# Main.net
KiCad netlist of a schematic drawn in Altium Designer
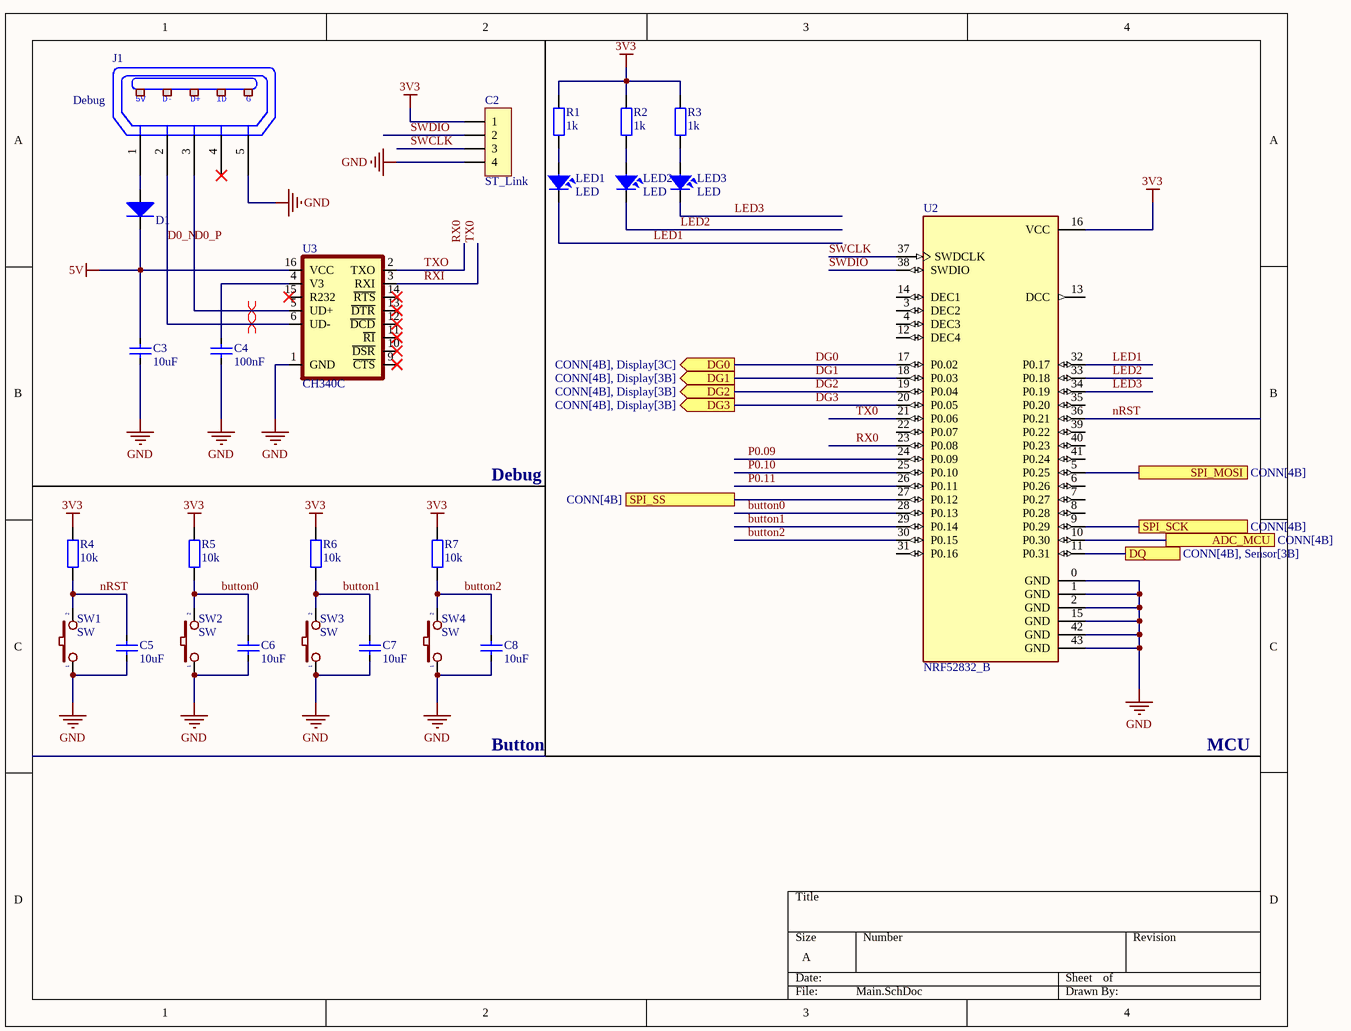
[diagram p0: Main.SchDoc]

(export (version "E")
  (design (tool "Eeschema 10.0.6"))
  (components
    (comp (ref "C2")
      (value "ST_Link")
      (footprint "J4-D1T")
      (description "WR-PHD 2.00 mm Socket Header")
      (fields
        (field (name "MANUFACTURER") "Würth Elektronik eiSos GmbH")
        (field (name "PARTNO") "62000411821")
        (field (name "CREATED BY") "Karrer Zheng")
      )
      (libsource (lib "Main") (part "JP4x1-2.0"))
    )
    (comp (ref "C3")
      (value "10uF")
      (footprint "CAP_0805")
      (description "Capacitor")
      (fields (field (name "PUBLISHER") "Altium Limited"))
      (libsource (lib "My Library") (part "CapSMD"))
    )
    (comp (ref "C4")
      (value "100nF")
      (footprint "CAP_0805")
      (description "Capacitor")
      (fields (field (name "PUBLISHER") "Altium Limited"))
      (libsource (lib "My Library") (part "CapSMD"))
    )
    (comp (ref "C5")
      (value "10uF")
      (footprint "CAP_0805")
      (description "Capacitor")
      (fields (field (name "PUBLISHER") "Altium Limited"))
      (libsource (lib "My Library") (part "CapSMD"))
    )
    (comp (ref "C6")
      (value "10uF")
      (footprint "CAP_0805")
      (description "Capacitor")
      (fields (field (name "PUBLISHER") "Altium Limited"))
      (libsource (lib "My Library") (part "CapSMD"))
    )
    (comp (ref "C7")
      (value "10uF")
      (footprint "CAP_0805")
      (description "Capacitor")
      (fields (field (name "PUBLISHER") "Altium Limited"))
      (libsource (lib "My Library") (part "CapSMD"))
    )
    (comp (ref "C8")
      (value "10uF")
      (footprint "CAP_0805")
      (description "Capacitor")
      (fields (field (name "PUBLISHER") "Altium Limited"))
      (libsource (lib "My Library") (part "CapSMD"))
    )
    (comp (ref "D1")
      (value "Diode SMD")
      (footprint "DIO-214AC(SMA)")
      (description "Default Diode")
      (fields (field (name "PUBLISHER") "Altium Limited"))
      (libsource (lib "My Library") (part "Diode SMD"))
    )
    (comp (ref "J1")
      (value "Debug")
      (footprint "USB-M1")
      (fields
        (field (name "MANUFACTURER") "FCI")
        (field (name "MANUFACTURER PART NUMBER") "10118193-0001LF")
        (field (name ".CREATOR") "MM")
        (field (name ".CHECKED PCB") "RF")
        (field (name ".CHECKED SCH") "MM")
      )
      (libsource (lib "My Library") (part "USB-5"))
    )
    (comp (ref "LED1")
      (value "LED")
      (footprint "LED-0805-Red")
      (description "LED Single colour Green and Red")
      (libsource (lib "My Library") (part "LED"))
    )
    (comp (ref "LED2")
      (value "LED")
      (footprint "LED-0805-Yellow")
      (description "LED Single colour Green and Red")
      (libsource (lib "My Library") (part "LED"))
    )
    (comp (ref "LED3")
      (value "LED")
      (footprint "LED-0805-Green")
      (description "LED Single colour Green and Red")
      (libsource (lib "My Library") (part "LED"))
    )
    (comp (ref "R1")
      (value "1k")
      (footprint "RES-SMD-0805")
      (description "Resistor SMD")
      (fields
        (field (name "MANUFACTURER") "Generic Components")
        (field (name "PUBLISHER") "Altium Hobart Technology Centre")
      )
      (libsource (lib "My Library") (part "Resistor - SMD"))
    )
    (comp (ref "R2")
      (value "1k")
      (footprint "RES-SMD-0805")
      (description "Resistor SMD")
      (fields
        (field (name "MANUFACTURER") "Generic Components")
        (field (name "PUBLISHER") "Altium Hobart Technology Centre")
      )
      (libsource (lib "My Library") (part "Resistor - SMD"))
    )
    (comp (ref "R3")
      (value "1k")
      (footprint "RES-SMD-0805")
      (description "Resistor SMD")
      (fields
        (field (name "MANUFACTURER") "Generic Components")
        (field (name "PUBLISHER") "Altium Hobart Technology Centre")
      )
      (libsource (lib "My Library") (part "Resistor - SMD"))
    )
    (comp (ref "R4")
      (value "10k")
      (footprint "RES-SMD-0805")
      (description "Resistor SMD")
      (fields
        (field (name "MANUFACTURER") "Generic Components")
        (field (name "PUBLISHER") "Altium Hobart Technology Centre")
      )
      (libsource (lib "My Library") (part "Resistor - SMD"))
    )
    (comp (ref "R5")
      (value "10k")
      (footprint "RES-SMD-0805")
      (description "Resistor SMD")
      (fields
        (field (name "MANUFACTURER") "Generic Components")
        (field (name "PUBLISHER") "Altium Hobart Technology Centre")
      )
      (libsource (lib "My Library") (part "Resistor - SMD"))
    )
    (comp (ref "R6")
      (value "10k")
      (footprint "RES-SMD-0805")
      (description "Resistor SMD")
      (fields
        (field (name "MANUFACTURER") "Generic Components")
        (field (name "PUBLISHER") "Altium Hobart Technology Centre")
      )
      (libsource (lib "My Library") (part "Resistor - SMD"))
    )
    (comp (ref "R7")
      (value "10k")
      (footprint "RES-SMD-0805")
      (description "Resistor SMD")
      (fields
        (field (name "MANUFACTURER") "Generic Components")
        (field (name "PUBLISHER") "Altium Hobart Technology Centre")
      )
      (libsource (lib "My Library") (part "Resistor - SMD"))
    )
    (comp (ref "SW1")
      (value "SW")
      (footprint "SW 3x2x4")
      (description "Switch button 2 pin")
      (libsource (lib "My Library") (part "SW2"))
    )
    (comp (ref "SW2")
      (value "SW")
      (footprint "SW2")
      (description "Switch button 2 pin")
      (libsource (lib "My Library") (part "SW2"))
    )
    (comp (ref "SW3")
      (value "SW")
      (footprint "SW2")
      (description "Switch button 2 pin")
      (libsource (lib "My Library") (part "SW2"))
    )
    (comp (ref "SW4")
      (value "SW")
      (footprint "SW2")
      (description "Switch button 2 pin")
      (libsource (lib "My Library") (part "SW2"))
    )
    (comp (ref "U2")
      (value "NRF52832_B")
      (footprint "NRF52832_B")
      (description "https://www.ebyte.com/product-view-news.aspx?id=239&=ds-tm")
      (libsource (lib "Main") (part "NRF52832_B"))
    )
    (comp (ref "U3")
      (value "CH340C")
      (footprint "SOP-16")
      (description "USB to serial chip CH340")
      (fields (field (name "MF") "WCH"))
      (libsource (lib "My Library") (part "CH340C"))
    )
  )
  (nets
    (net (code "1") (name "/ADC_MCU") (class "Default")
      (node (ref "U2") (pin "10") (pinfunction "P0.30_10") (pintype "bidirectional"))
    )
    (net (code "2") (name "/D0_N") (class "Default")
      (node (ref "J1") (pin "2") (pinfunction "P2_2") (pintype "passive"))
      (node (ref "U3") (pin "6") (pinfunction "UD-_6") (pintype "bidirectional"))
    )
    (net (code "3") (name "/D0_P") (class "Default")
      (node (ref "J1") (pin "3") (pinfunction "P3_3") (pintype "passive"))
      (node (ref "U3") (pin "5") (pinfunction "UD+_5") (pintype "bidirectional"))
    )
    (net (code "4") (name "/DG0") (class "Default")
      (node (ref "U2") (pin "17") (pinfunction "P0.02_17") (pintype "bidirectional"))
    )
    (net (code "5") (name "/DG1") (class "Default")
      (node (ref "U2") (pin "18") (pinfunction "P0.03_18") (pintype "bidirectional"))
    )
    (net (code "6") (name "/DG2") (class "Default")
      (node (ref "U2") (pin "19") (pinfunction "P0.04_19") (pintype "bidirectional"))
    )
    (net (code "7") (name "/DG3") (class "Default")
      (node (ref "U2") (pin "20") (pinfunction "P0.05_20") (pintype "bidirectional"))
    )
    (net (code "8") (name "/DQ") (class "Default")
      (node (ref "U2") (pin "11") (pinfunction "P0.31_11") (pintype "bidirectional"))
    )
    (net (code "9") (name "/LED1") (class "Default")
      (node (ref "LED1") (pin "2") (pinfunction "2_2") (pintype "passive"))
      (node (ref "U2") (pin "32") (pinfunction "P0.17_32") (pintype "bidirectional"))
    )
    (net (code "10") (name "/LED2") (class "Default")
      (node (ref "LED2") (pin "2") (pinfunction "2_2") (pintype "passive"))
      (node (ref "U2") (pin "33") (pinfunction "P0.18_33") (pintype "bidirectional"))
    )
    (net (code "11") (name "/LED3") (class "Default")
      (node (ref "LED3") (pin "2") (pinfunction "2_2") (pintype "passive"))
      (node (ref "U2") (pin "34") (pinfunction "P0.19_34") (pintype "bidirectional"))
    )
    (net (code "12") (name "/P0.09") (class "Default")
      (node (ref "U2") (pin "24") (pinfunction "P0.09_24") (pintype "bidirectional"))
    )
    (net (code "13") (name "/P0.10") (class "Default")
      (node (ref "U2") (pin "25") (pinfunction "P0.10_25") (pintype "bidirectional"))
    )
    (net (code "14") (name "/P0.11") (class "Default")
      (node (ref "U2") (pin "26") (pinfunction "P0.11_26") (pintype "bidirectional"))
    )
    (net (code "15") (name "/RX0") (class "Default")
      (node (ref "U2") (pin "23") (pinfunction "P0.08_23") (pintype "bidirectional"))
      (node (ref "U3") (pin "2") (pinfunction "TXO_2") (pintype "bidirectional"))
    )
    (net (code "16") (name "/RXI") (class "Default")
      (node (ref "U2") (pin "21") (pinfunction "P0.06_21") (pintype "bidirectional"))
      (node (ref "U3") (pin "3") (pinfunction "RXI_3") (pintype "bidirectional"))
    )
    (net (code "17") (name "/SPI_MOSI") (class "Default")
      (node (ref "U2") (pin "5") (pinfunction "P0.25_5") (pintype "bidirectional"))
    )
    (net (code "18") (name "/SPI_SCK") (class "Default")
      (node (ref "U2") (pin "9") (pinfunction "P0.29_9") (pintype "bidirectional"))
    )
    (net (code "19") (name "/SPI_SS") (class "Default")
      (node (ref "U2") (pin "27") (pinfunction "P0.12_27") (pintype "bidirectional"))
    )
    (net (code "20") (name "/SWCLK") (class "Default")
      (node (ref "C2") (pin "3") (pinfunction "3_3") (pintype "passive"))
      (node (ref "U2") (pin "37") (pinfunction "SWDCLK_37") (pintype "input"))
    )
    (net (code "21") (name "/SWDIO") (class "Default")
      (node (ref "C2") (pin "2") (pinfunction "2_2") (pintype "passive"))
      (node (ref "U2") (pin "38") (pinfunction "SWDIO_38") (pintype "bidirectional"))
    )
    (net (code "22") (name "/button0") (class "Default")
      (node (ref "C6") (pin "2") (pinfunction "2_2") (pintype "passive"))
      (node (ref "R5") (pin "2") (pinfunction "2_2") (pintype "passive"))
      (node (ref "SW2") (pin "2") (pinfunction "2_2") (pintype "passive"))
      (node (ref "U2") (pin "28") (pinfunction "P0.13_28") (pintype "bidirectional"))
    )
    (net (code "23") (name "/button1") (class "Default")
      (node (ref "C7") (pin "2") (pinfunction "2_2") (pintype "passive"))
      (node (ref "R6") (pin "2") (pinfunction "2_2") (pintype "passive"))
      (node (ref "SW3") (pin "2") (pinfunction "2_2") (pintype "passive"))
      (node (ref "U2") (pin "29") (pinfunction "P0.14_29") (pintype "bidirectional"))
    )
    (net (code "24") (name "/button2") (class "Default")
      (node (ref "C8") (pin "2") (pinfunction "2_2") (pintype "passive"))
      (node (ref "R7") (pin "2") (pinfunction "2_2") (pintype "passive"))
      (node (ref "SW4") (pin "2") (pinfunction "2_2") (pintype "passive"))
      (node (ref "U2") (pin "30") (pinfunction "P0.15_30") (pintype "bidirectional"))
    )
    (net (code "25") (name "/nRST") (class "Default")
      (node (ref "C5") (pin "2") (pinfunction "2_2") (pintype "passive"))
      (node (ref "R4") (pin "2") (pinfunction "2_2") (pintype "passive"))
      (node (ref "SW1") (pin "2") (pinfunction "2_2") (pintype "passive"))
      (node (ref "U2") (pin "36") (pinfunction "P0.21_36") (pintype "bidirectional"))
    )
    (net (code "26") (name "3V3") (class "Default")
      (node (ref "C2") (pin "1") (pinfunction "1_1") (pintype "passive"))
      (node (ref "R1") (pin "1") (pinfunction "1_1") (pintype "passive"))
      (node (ref "R2") (pin "1") (pinfunction "1_1") (pintype "passive"))
      (node (ref "R3") (pin "1") (pinfunction "1_1") (pintype "passive"))
      (node (ref "R4") (pin "1") (pinfunction "1_1") (pintype "passive"))
      (node (ref "R5") (pin "1") (pinfunction "1_1") (pintype "passive"))
      (node (ref "R6") (pin "1") (pinfunction "1_1") (pintype "passive"))
      (node (ref "R7") (pin "1") (pinfunction "1_1") (pintype "passive"))
      (node (ref "U2") (pin "16") (pinfunction "VCC_16") (pintype "power_in"))
    )
    (net (code "27") (name "5V") (class "Default")
      (node (ref "C3") (pin "2") (pinfunction "2_2") (pintype "passive"))
      (node (ref "D1") (pin "2") (pinfunction "K_2") (pintype "passive"))
      (node (ref "U3") (pin "16") (pinfunction "VCC_16") (pintype "bidirectional"))
    )
    (net (code "28") (name "GND") (class "Default")
      (node (ref "C2") (pin "4") (pinfunction "4_4") (pintype "passive"))
      (node (ref "C3") (pin "1") (pinfunction "1_1") (pintype "passive"))
      (node (ref "C4") (pin "1") (pinfunction "1_1") (pintype "passive"))
      (node (ref "C5") (pin "1") (pinfunction "1_1") (pintype "passive"))
      (node (ref "C6") (pin "1") (pinfunction "1_1") (pintype "passive"))
      (node (ref "C7") (pin "1") (pinfunction "1_1") (pintype "passive"))
      (node (ref "C8") (pin "1") (pinfunction "1_1") (pintype "passive"))
      (node (ref "J1") (pin "5") (pinfunction "P5_5") (pintype "passive"))
      (node (ref "SW1") (pin "1") (pinfunction "1_1") (pintype "passive"))
      (node (ref "SW2") (pin "1") (pinfunction "1_1") (pintype "passive"))
      (node (ref "SW3") (pin "1") (pinfunction "1_1") (pintype "passive"))
      (node (ref "SW4") (pin "1") (pinfunction "1_1") (pintype "passive"))
      (node (ref "U2") (pin "0") (pinfunction "GND_0") (pintype "power_in"))
      (node (ref "U2") (pin "1") (pinfunction "GND_1") (pintype "power_in"))
      (node (ref "U2") (pin "15") (pinfunction "GND_15") (pintype "power_in"))
      (node (ref "U2") (pin "2") (pinfunction "GND_2") (pintype "power_in"))
      (node (ref "U2") (pin "42") (pinfunction "GND_42") (pintype "power_in"))
      (node (ref "U2") (pin "43") (pinfunction "GND_43") (pintype "power_in"))
      (node (ref "U3") (pin "1") (pinfunction "GND_1") (pintype "bidirectional"))
    )
    (net (code "29") (name "Net-(D1-A)") (class "Default")
      (node (ref "D1") (pin "1") (pinfunction "A_1") (pintype "passive"))
      (node (ref "J1") (pin "1") (pinfunction "P1_1") (pintype "passive"))
    )
    (net (code "30") (name "Net-(LED1-Pad1)") (class "Default")
      (node (ref "LED1") (pin "1") (pinfunction "1_1") (pintype "passive"))
      (node (ref "R1") (pin "2") (pinfunction "2_2") (pintype "passive"))
    )
    (net (code "31") (name "Net-(LED2-Pad1)") (class "Default")
      (node (ref "LED2") (pin "1") (pinfunction "1_1") (pintype "passive"))
      (node (ref "R2") (pin "2") (pinfunction "2_2") (pintype "passive"))
    )
    (net (code "32") (name "Net-(LED3-Pad1)") (class "Default")
      (node (ref "LED3") (pin "1") (pinfunction "1_1") (pintype "passive"))
      (node (ref "R3") (pin "2") (pinfunction "2_2") (pintype "passive"))
    )
    (net (code "33") (name "Net-(U3-V3)") (class "Default")
      (node (ref "C4") (pin "2") (pinfunction "2_2") (pintype "passive"))
      (node (ref "U3") (pin "4") (pinfunction "V3_4") (pintype "bidirectional"))
    )
    (net (code "34") (name "unconnected-(J1-P4-Pad4)") (class "Default")
      (node (ref "J1") (pin "4") (pinfunction "P4_4") (pintype "passive+no_connect"))
    )
    (net (code "35") (name "unconnected-(U2-DCC-Pad13)") (class "Default")
      (node (ref "U2") (pin "13") (pinfunction "DCC_13") (pintype "output"))
    )
    (net (code "36") (name "unconnected-(U2-DEC1-Pad14)") (class "Default")
      (node (ref "U2") (pin "14") (pinfunction "DEC1_14") (pintype "bidirectional"))
    )
    (net (code "37") (name "unconnected-(U2-DEC2-Pad3)") (class "Default")
      (node (ref "U2") (pin "3") (pinfunction "DEC2_3") (pintype "bidirectional"))
    )
    (net (code "38") (name "unconnected-(U2-DEC3-Pad4)") (class "Default")
      (node (ref "U2") (pin "4") (pinfunction "DEC3_4") (pintype "bidirectional"))
    )
    (net (code "39") (name "unconnected-(U2-DEC4-Pad12)") (class "Default")
      (node (ref "U2") (pin "12") (pinfunction "DEC4_12") (pintype "bidirectional"))
    )
    (net (code "40") (name "unconnected-(U2-P0.07-Pad22)") (class "Default")
      (node (ref "U2") (pin "22") (pinfunction "P0.07_22") (pintype "bidirectional"))
    )
    (net (code "41") (name "unconnected-(U2-P0.16-Pad31)") (class "Default")
      (node (ref "U2") (pin "31") (pinfunction "P0.16_31") (pintype "bidirectional"))
    )
    (net (code "42") (name "unconnected-(U2-P0.20-Pad35)") (class "Default")
      (node (ref "U2") (pin "35") (pinfunction "P0.20_35") (pintype "bidirectional"))
    )
    (net (code "43") (name "unconnected-(U2-P0.22-Pad39)") (class "Default")
      (node (ref "U2") (pin "39") (pinfunction "P0.22_39") (pintype "bidirectional"))
    )
    (net (code "44") (name "unconnected-(U2-P0.23-Pad40)") (class "Default")
      (node (ref "U2") (pin "40") (pinfunction "P0.23_40") (pintype "bidirectional"))
    )
    (net (code "45") (name "unconnected-(U2-P0.24-Pad41)") (class "Default")
      (node (ref "U2") (pin "41") (pinfunction "P0.24_41") (pintype "bidirectional"))
    )
    (net (code "46") (name "unconnected-(U2-P0.26-Pad6)") (class "Default")
      (node (ref "U2") (pin "6") (pinfunction "P0.26_6") (pintype "bidirectional"))
    )
    (net (code "47") (name "unconnected-(U2-P0.27-Pad7)") (class "Default")
      (node (ref "U2") (pin "7") (pinfunction "P0.27_7") (pintype "bidirectional"))
    )
    (net (code "48") (name "unconnected-(U2-P0.28-Pad8)") (class "Default")
      (node (ref "U2") (pin "8") (pinfunction "P0.28_8") (pintype "bidirectional"))
    )
    (net (code "49") (name "unconnected-(U3-R232-Pad15)") (class "Default")
      (node (ref "U3") (pin "15") (pinfunction "R232_15") (pintype "bidirectional+no_connect"))
    )
    (net (code "50") (name "unconnected-(U3-~{CTS}-Pad9)") (class "Default")
      (node (ref "U3") (pin "9") (pinfunction "~{CTS}_9") (pintype "bidirectional+no_connect"))
    )
    (net (code "51") (name "unconnected-(U3-~{DCD}-Pad12)") (class "Default")
      (node (ref "U3") (pin "12") (pinfunction "~{DCD}_12") (pintype "bidirectional+no_connect"))
    )
    (net (code "52") (name "unconnected-(U3-~{DSR}-Pad10)") (class "Default")
      (node (ref "U3") (pin "10") (pinfunction "~{DSR}_10") (pintype "bidirectional+no_connect"))
    )
    (net (code "53") (name "unconnected-(U3-~{DTR}-Pad13)") (class "Default")
      (node (ref "U3") (pin "13") (pinfunction "~{DTR}_13") (pintype "bidirectional+no_connect"))
    )
    (net (code "54") (name "unconnected-(U3-~{RI}-Pad11)") (class "Default")
      (node (ref "U3") (pin "11") (pinfunction "~{RI}_11") (pintype "bidirectional+no_connect"))
    )
    (net (code "55") (name "unconnected-(U3-~{RTS}-Pad14)") (class "Default")
      (node (ref "U3") (pin "14") (pinfunction "~{RTS}_14") (pintype "bidirectional+no_connect"))
    )
  )
)
